# JUMP_PI.net
KiCad netlist of a schematic drawn in Altium Designer
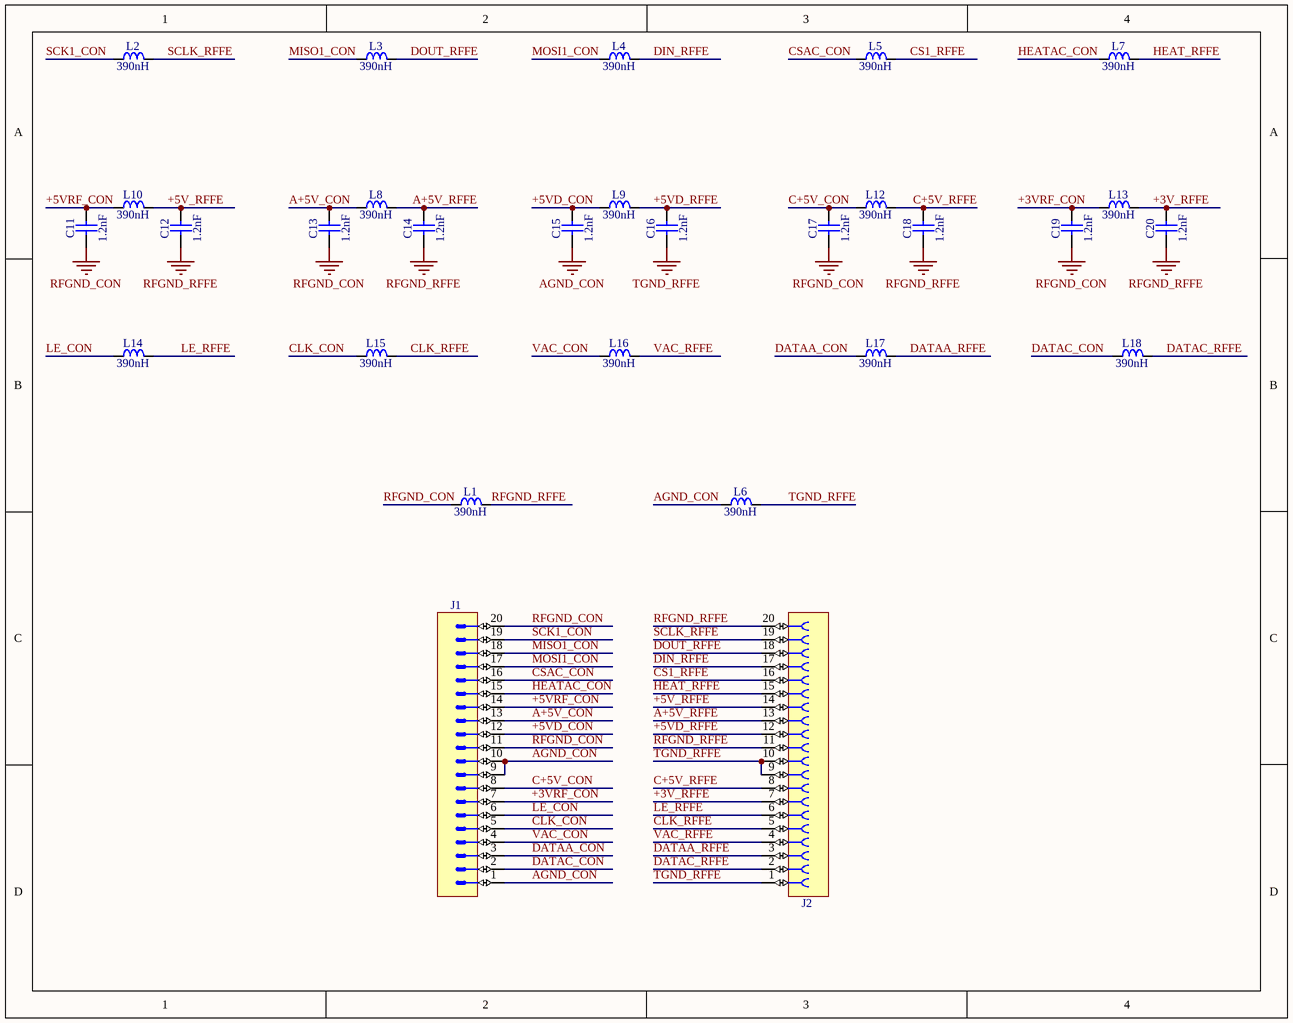
[diagram p0: JUMP_PI.schdoc]

(export (version "E")
  (design (tool "Eeschema 10.0.6"))
  (components
    (comp (ref "C11")
      (value "1.2nF")
      (footprint "CAPC2012X135N")
      (description "Non-polarised capacitor")
      (fields
        (field (name "PART NUMBER") "CC0805_1.2NF_50V_10%_X7R")
        (field (name "VOLTAGE") "50V")
        (field (name "AUTHOR") "CERN DEM JLC")
      )
      (libsource (lib "Capacitors") (part "Capacitor - non polarized"))
    )
    (comp (ref "C12")
      (value "1.2nF")
      (footprint "CAPC2012X135N")
      (description "Non-polarised capacitor")
      (fields
        (field (name "PART NUMBER") "CC0805_1.2NF_50V_10%_X7R")
        (field (name "VOLTAGE") "50V")
        (field (name "AUTHOR") "CERN DEM JLC")
      )
      (libsource (lib "Capacitors") (part "Capacitor - non polarized"))
    )
    (comp (ref "C13")
      (value "1.2nF")
      (footprint "CAPC2012X135N")
      (description "Non-polarised capacitor")
      (fields
        (field (name "PART NUMBER") "CC0805_1.2NF_50V_10%_X7R")
        (field (name "VOLTAGE") "50V")
        (field (name "AUTHOR") "CERN DEM JLC")
      )
      (libsource (lib "Capacitors") (part "Capacitor - non polarized"))
    )
    (comp (ref "C14")
      (value "1.2nF")
      (footprint "CAPC2012X135N")
      (description "Non-polarised capacitor")
      (fields
        (field (name "PART NUMBER") "CC0805_1.2NF_50V_10%_X7R")
        (field (name "VOLTAGE") "50V")
        (field (name "AUTHOR") "CERN DEM JLC")
      )
      (libsource (lib "Capacitors") (part "Capacitor - non polarized"))
    )
    (comp (ref "C15")
      (value "1.2nF")
      (footprint "CAPC2012X135N")
      (description "Non-polarised capacitor")
      (fields
        (field (name "PART NUMBER") "CC0805_1.2NF_50V_10%_X7R")
        (field (name "VOLTAGE") "50V")
        (field (name "AUTHOR") "CERN DEM JLC")
      )
      (libsource (lib "Capacitors") (part "Capacitor - non polarized"))
    )
    (comp (ref "C16")
      (value "1.2nF")
      (footprint "CAPC2012X135N")
      (description "Non-polarised capacitor")
      (fields
        (field (name "PART NUMBER") "CC0805_1.2NF_50V_10%_X7R")
        (field (name "VOLTAGE") "50V")
        (field (name "AUTHOR") "CERN DEM JLC")
      )
      (libsource (lib "Capacitors") (part "Capacitor - non polarized"))
    )
    (comp (ref "C17")
      (value "1.2nF")
      (footprint "CAPC2012X135N")
      (description "Non-polarised capacitor")
      (fields
        (field (name "PART NUMBER") "CC0805_1.2NF_50V_10%_X7R")
        (field (name "VOLTAGE") "50V")
        (field (name "AUTHOR") "CERN DEM JLC")
      )
      (libsource (lib "Capacitors") (part "Capacitor - non polarized"))
    )
    (comp (ref "C18")
      (value "1.2nF")
      (footprint "CAPC2012X135N")
      (description "Non-polarised capacitor")
      (fields
        (field (name "PART NUMBER") "CC0805_1.2NF_50V_10%_X7R")
        (field (name "VOLTAGE") "50V")
        (field (name "AUTHOR") "CERN DEM JLC")
      )
      (libsource (lib "Capacitors") (part "Capacitor - non polarized"))
    )
    (comp (ref "C19")
      (value "1.2nF")
      (footprint "CAPC2012X135N")
      (description "Non-polarised capacitor")
      (fields
        (field (name "PART NUMBER") "CC0805_1.2NF_50V_10%_X7R")
        (field (name "VOLTAGE") "50V")
        (field (name "AUTHOR") "CERN DEM JLC")
      )
      (libsource (lib "Capacitors") (part "Capacitor - non polarized"))
    )
    (comp (ref "C20")
      (value "1.2nF")
      (footprint "CAPC2012X135N")
      (description "Non-polarised capacitor")
      (fields
        (field (name "PART NUMBER") "CC0805_1.2NF_50V_10%_X7R")
        (field (name "VOLTAGE") "50V")
        (field (name "AUTHOR") "CERN DEM JLC")
      )
      (libsource (lib "Capacitors") (part "Capacitor - non polarized"))
    )
    (comp (ref "J1")
      (value "Header 20")
      (footprint "SAMTEC_TFM-120-01-L-S-RA")
      (description "Connector 20 Male")
      (fields
        (field (name "MANUFACTURER") "SAMTEC")
        (field (name "MANUFACTURER PART NUMBER") "TFM-120-01-L-S-RA")
        (field (name "AUTHOR") "LNLS DIG FCS")
      )
      (libsource (lib "Connectors_LNLS") (part "Connector 20 Male"))
    )
    (comp (ref "J2")
      (value "Header 20")
      (footprint "SAMTEC_SFM-120-02-S-SH")
      (description "Connector 20 Female")
      (fields
        (field (name "PART NUMBER") "SAMTEC_SFM-120-02-S-SH")
        (field (name "MANUFACTURER") "SAMTEC")
        (field (name "AUTHOR") "LNLS DIG FCS")
      )
      (libsource (lib "Connectors_LNLS") (part "Connector 20 Female"))
    )
    (comp (ref "L1")
      (value "390nH")
      (footprint "IND_ABRACON_AISC-0603")
      (description "Inductor")
      (fields
        (field (name "PART NUMBER") "IND_390NH_5%_ABRACON_AISC-0603")
        (field (name "POWER") "120mA")
        (field (name "AUTHOR") "CERN DEM JLC")
      )
      (libsource (lib "Inductors & Transformers") (part "Inductor"))
    )
    (comp (ref "L2")
      (value "390nH")
      (footprint "IND_ABRACON_AISC-0603")
      (description "Inductor")
      (fields
        (field (name "PART NUMBER") "IND_390NH_5%_ABRACON_AISC-0603")
        (field (name "POWER") "120mA")
        (field (name "AUTHOR") "CERN DEM JLC")
      )
      (libsource (lib "Inductors & Transformers") (part "Inductor"))
    )
    (comp (ref "L3")
      (value "390nH")
      (footprint "IND_ABRACON_AISC-0603")
      (description "Inductor")
      (fields
        (field (name "PART NUMBER") "IND_390NH_5%_ABRACON_AISC-0603")
        (field (name "POWER") "120mA")
        (field (name "AUTHOR") "CERN DEM JLC")
      )
      (libsource (lib "Inductors & Transformers") (part "Inductor"))
    )
    (comp (ref "L4")
      (value "390nH")
      (footprint "IND_ABRACON_AISC-0603")
      (description "Inductor")
      (fields
        (field (name "PART NUMBER") "IND_390NH_5%_ABRACON_AISC-0603")
        (field (name "POWER") "120mA")
        (field (name "AUTHOR") "CERN DEM JLC")
      )
      (libsource (lib "Inductors & Transformers") (part "Inductor"))
    )
    (comp (ref "L5")
      (value "390nH")
      (footprint "IND_ABRACON_AISC-0603")
      (description "Inductor")
      (fields
        (field (name "PART NUMBER") "IND_390NH_5%_ABRACON_AISC-0603")
        (field (name "POWER") "120mA")
        (field (name "AUTHOR") "CERN DEM JLC")
      )
      (libsource (lib "Inductors & Transformers") (part "Inductor"))
    )
    (comp (ref "L6")
      (value "390nH")
      (footprint "IND_ABRACON_AISC-0603")
      (description "Inductor")
      (fields
        (field (name "PART NUMBER") "IND_390NH_5%_ABRACON_AISC-0603")
        (field (name "POWER") "120mA")
        (field (name "AUTHOR") "CERN DEM JLC")
      )
      (libsource (lib "Inductors & Transformers") (part "Inductor"))
    )
    (comp (ref "L7")
      (value "390nH")
      (footprint "IND_ABRACON_AISC-0603")
      (description "Inductor")
      (fields
        (field (name "PART NUMBER") "IND_390NH_5%_ABRACON_AISC-0603")
        (field (name "POWER") "120mA")
        (field (name "AUTHOR") "CERN DEM JLC")
      )
      (libsource (lib "Inductors & Transformers") (part "Inductor"))
    )
    (comp (ref "L8")
      (value "390nH")
      (footprint "IND_ABRACON_AISC-0603")
      (description "Inductor")
      (fields
        (field (name "PART NUMBER") "IND_390NH_5%_ABRACON_AISC-0603")
        (field (name "POWER") "120mA")
        (field (name "AUTHOR") "CERN DEM JLC")
      )
      (libsource (lib "Inductors & Transformers") (part "Inductor"))
    )
    (comp (ref "L9")
      (value "390nH")
      (footprint "IND_ABRACON_AISC-0603")
      (description "Inductor")
      (fields
        (field (name "PART NUMBER") "IND_390NH_5%_ABRACON_AISC-0603")
        (field (name "POWER") "120mA")
        (field (name "AUTHOR") "CERN DEM JLC")
      )
      (libsource (lib "Inductors & Transformers") (part "Inductor"))
    )
    (comp (ref "L10")
      (value "390nH")
      (footprint "IND_ABRACON_AISC-0603")
      (description "Inductor")
      (fields
        (field (name "PART NUMBER") "IND_390NH_5%_ABRACON_AISC-0603")
        (field (name "POWER") "120mA")
        (field (name "AUTHOR") "CERN DEM JLC")
      )
      (libsource (lib "Inductors & Transformers") (part "Inductor"))
    )
    (comp (ref "L12")
      (value "390nH")
      (footprint "IND_ABRACON_AISC-0603")
      (description "Inductor")
      (fields
        (field (name "PART NUMBER") "IND_390NH_5%_ABRACON_AISC-0603")
        (field (name "POWER") "120mA")
        (field (name "AUTHOR") "CERN DEM JLC")
      )
      (libsource (lib "Inductors & Transformers") (part "Inductor"))
    )
    (comp (ref "L13")
      (value "390nH")
      (footprint "IND_ABRACON_AISC-0603")
      (description "Inductor")
      (fields
        (field (name "PART NUMBER") "IND_390NH_5%_ABRACON_AISC-0603")
        (field (name "POWER") "120mA")
        (field (name "AUTHOR") "CERN DEM JLC")
      )
      (libsource (lib "Inductors & Transformers") (part "Inductor"))
    )
    (comp (ref "L14")
      (value "390nH")
      (footprint "IND_ABRACON_AISC-0603")
      (description "Inductor")
      (fields
        (field (name "PART NUMBER") "IND_390NH_5%_ABRACON_AISC-0603")
        (field (name "POWER") "120mA")
        (field (name "AUTHOR") "CERN DEM JLC")
      )
      (libsource (lib "Inductors & Transformers") (part "Inductor"))
    )
    (comp (ref "L15")
      (value "390nH")
      (footprint "IND_ABRACON_AISC-0603")
      (description "Inductor")
      (fields
        (field (name "PART NUMBER") "IND_390NH_5%_ABRACON_AISC-0603")
        (field (name "POWER") "120mA")
        (field (name "AUTHOR") "CERN DEM JLC")
      )
      (libsource (lib "Inductors & Transformers") (part "Inductor"))
    )
    (comp (ref "L16")
      (value "390nH")
      (footprint "IND_ABRACON_AISC-0603")
      (description "Inductor")
      (fields
        (field (name "PART NUMBER") "IND_390NH_5%_ABRACON_AISC-0603")
        (field (name "POWER") "120mA")
        (field (name "AUTHOR") "CERN DEM JLC")
      )
      (libsource (lib "Inductors & Transformers") (part "Inductor"))
    )
    (comp (ref "L17")
      (value "390nH")
      (footprint "IND_ABRACON_AISC-0603")
      (description "Inductor")
      (fields
        (field (name "PART NUMBER") "IND_390NH_5%_ABRACON_AISC-0603")
        (field (name "POWER") "120mA")
        (field (name "AUTHOR") "CERN DEM JLC")
      )
      (libsource (lib "Inductors & Transformers") (part "Inductor"))
    )
    (comp (ref "L18")
      (value "390nH")
      (footprint "IND_ABRACON_AISC-0603")
      (description "Inductor")
      (fields
        (field (name "PART NUMBER") "IND_390NH_5%_ABRACON_AISC-0603")
        (field (name "POWER") "120mA")
        (field (name "AUTHOR") "CERN DEM JLC")
      )
      (libsource (lib "Inductors & Transformers") (part "Inductor"))
    )
  )
  (nets
    (net (code "1") (name "/+3VRF_CON") (class "Default")
      (node (ref "C19") (pin "2") (pinfunction "2_2") (pintype "passive"))
      (node (ref "J1") (pin "7") (pinfunction "7_7") (pintype "bidirectional"))
      (node (ref "L13") (pin "1") (pinfunction "1_1") (pintype "passive"))
    )
    (net (code "2") (name "/+3V_RFFE") (class "Default")
      (node (ref "C20") (pin "2") (pinfunction "2_2") (pintype "passive"))
      (node (ref "J2") (pin "7") (pinfunction "7_7") (pintype "bidirectional"))
      (node (ref "L13") (pin "2") (pinfunction "2_2") (pintype "passive"))
    )
    (net (code "3") (name "/+5VD_CON") (class "Default")
      (node (ref "C15") (pin "2") (pinfunction "2_2") (pintype "passive"))
      (node (ref "J1") (pin "12") (pinfunction "12_12") (pintype "bidirectional"))
      (node (ref "L9") (pin "1") (pinfunction "1_1") (pintype "passive"))
    )
    (net (code "4") (name "/+5VD_RFFE") (class "Default")
      (node (ref "C16") (pin "2") (pinfunction "2_2") (pintype "passive"))
      (node (ref "J2") (pin "12") (pinfunction "12_12") (pintype "bidirectional"))
      (node (ref "L9") (pin "2") (pinfunction "2_2") (pintype "passive"))
    )
    (net (code "5") (name "/+5VRF_CON") (class "Default")
      (node (ref "C11") (pin "2") (pinfunction "2_2") (pintype "passive"))
      (node (ref "J1") (pin "14") (pinfunction "14_14") (pintype "bidirectional"))
      (node (ref "L10") (pin "1") (pinfunction "1_1") (pintype "passive"))
    )
    (net (code "6") (name "/+5V_RFFE") (class "Default")
      (node (ref "C12") (pin "2") (pinfunction "2_2") (pintype "passive"))
      (node (ref "J2") (pin "14") (pinfunction "14_14") (pintype "bidirectional"))
      (node (ref "L10") (pin "2") (pinfunction "2_2") (pintype "passive"))
    )
    (net (code "7") (name "/A+5V_CON") (class "Default")
      (node (ref "C13") (pin "2") (pinfunction "2_2") (pintype "passive"))
      (node (ref "J1") (pin "13") (pinfunction "13_13") (pintype "bidirectional"))
      (node (ref "L8") (pin "1") (pinfunction "1_1") (pintype "passive"))
    )
    (net (code "8") (name "/A+5V_RFFE") (class "Default")
      (node (ref "C14") (pin "2") (pinfunction "2_2") (pintype "passive"))
      (node (ref "J2") (pin "13") (pinfunction "13_13") (pintype "bidirectional"))
      (node (ref "L8") (pin "2") (pinfunction "2_2") (pintype "passive"))
    )
    (net (code "9") (name "/C+5V_CON") (class "Default")
      (node (ref "C17") (pin "2") (pinfunction "2_2") (pintype "passive"))
      (node (ref "J1") (pin "8") (pinfunction "8_8") (pintype "bidirectional"))
      (node (ref "L12") (pin "1") (pinfunction "1_1") (pintype "passive"))
    )
    (net (code "10") (name "/C+5V_RFFE") (class "Default")
      (node (ref "C18") (pin "2") (pinfunction "2_2") (pintype "passive"))
      (node (ref "J2") (pin "8") (pinfunction "8_8") (pintype "bidirectional"))
      (node (ref "L12") (pin "2") (pinfunction "2_2") (pintype "passive"))
    )
    (net (code "11") (name "/CLK_CON") (class "Default")
      (node (ref "J1") (pin "5") (pinfunction "5_5") (pintype "bidirectional"))
      (node (ref "L15") (pin "1") (pinfunction "1_1") (pintype "passive"))
    )
    (net (code "12") (name "/CLK_RFFE") (class "Default")
      (node (ref "J2") (pin "5") (pinfunction "5_5") (pintype "bidirectional"))
      (node (ref "L15") (pin "2") (pinfunction "2_2") (pintype "passive"))
    )
    (net (code "13") (name "/CS1_RFFE") (class "Default")
      (node (ref "J2") (pin "16") (pinfunction "16_16") (pintype "bidirectional"))
      (node (ref "L5") (pin "2") (pinfunction "2_2") (pintype "passive"))
    )
    (net (code "14") (name "/CSAC_CON") (class "Default")
      (node (ref "J1") (pin "16") (pinfunction "16_16") (pintype "bidirectional"))
      (node (ref "L5") (pin "1") (pinfunction "1_1") (pintype "passive"))
    )
    (net (code "15") (name "/DATAA_CON") (class "Default")
      (node (ref "J1") (pin "3") (pinfunction "3_3") (pintype "bidirectional"))
      (node (ref "L17") (pin "1") (pinfunction "1_1") (pintype "passive"))
    )
    (net (code "16") (name "/DATAA_RFFE") (class "Default")
      (node (ref "J2") (pin "3") (pinfunction "3_3") (pintype "bidirectional"))
      (node (ref "L17") (pin "2") (pinfunction "2_2") (pintype "passive"))
    )
    (net (code "17") (name "/DATAC_CON") (class "Default")
      (node (ref "J1") (pin "2") (pinfunction "2_2") (pintype "bidirectional"))
      (node (ref "L18") (pin "1") (pinfunction "1_1") (pintype "passive"))
    )
    (net (code "18") (name "/DATAC_RFFE") (class "Default")
      (node (ref "J2") (pin "2") (pinfunction "2_2") (pintype "bidirectional"))
      (node (ref "L18") (pin "2") (pinfunction "2_2") (pintype "passive"))
    )
    (net (code "19") (name "/DIN_RFFE") (class "Default")
      (node (ref "J2") (pin "17") (pinfunction "17_17") (pintype "bidirectional"))
      (node (ref "L4") (pin "2") (pinfunction "2_2") (pintype "passive"))
    )
    (net (code "20") (name "/DOUT_RFFE") (class "Default")
      (node (ref "J2") (pin "18") (pinfunction "18_18") (pintype "bidirectional"))
      (node (ref "L3") (pin "2") (pinfunction "2_2") (pintype "passive"))
    )
    (net (code "21") (name "/HEATAC_CON") (class "Default")
      (node (ref "J1") (pin "15") (pinfunction "15_15") (pintype "bidirectional"))
      (node (ref "L7") (pin "1") (pinfunction "1_1") (pintype "passive"))
    )
    (net (code "22") (name "/HEAT_RFFE") (class "Default")
      (node (ref "J2") (pin "15") (pinfunction "15_15") (pintype "bidirectional"))
      (node (ref "L7") (pin "2") (pinfunction "2_2") (pintype "passive"))
    )
    (net (code "23") (name "/LE_CON") (class "Default")
      (node (ref "J1") (pin "6") (pinfunction "6_6") (pintype "bidirectional"))
      (node (ref "L14") (pin "1") (pinfunction "1_1") (pintype "passive"))
    )
    (net (code "24") (name "/LE_RFFE") (class "Default")
      (node (ref "J2") (pin "6") (pinfunction "6_6") (pintype "bidirectional"))
      (node (ref "L14") (pin "2") (pinfunction "2_2") (pintype "passive"))
    )
    (net (code "25") (name "/MISO1_CON") (class "Default")
      (node (ref "J1") (pin "18") (pinfunction "18_18") (pintype "bidirectional"))
      (node (ref "L3") (pin "1") (pinfunction "1_1") (pintype "passive"))
    )
    (net (code "26") (name "/MOSI1_CON") (class "Default")
      (node (ref "J1") (pin "17") (pinfunction "17_17") (pintype "bidirectional"))
      (node (ref "L4") (pin "1") (pinfunction "1_1") (pintype "passive"))
    )
    (net (code "27") (name "/SCK1_CON") (class "Default")
      (node (ref "J1") (pin "19") (pinfunction "19_19") (pintype "bidirectional"))
      (node (ref "L2") (pin "1") (pinfunction "1_1") (pintype "passive"))
    )
    (net (code "28") (name "/SCLK_RFFE") (class "Default")
      (node (ref "J2") (pin "19") (pinfunction "19_19") (pintype "bidirectional"))
      (node (ref "L2") (pin "2") (pinfunction "2_2") (pintype "passive"))
    )
    (net (code "29") (name "/VAC_CON") (class "Default")
      (node (ref "J1") (pin "4") (pinfunction "4_4") (pintype "bidirectional"))
      (node (ref "L16") (pin "1") (pinfunction "1_1") (pintype "passive"))
    )
    (net (code "30") (name "/VAC_RFFE") (class "Default")
      (node (ref "J2") (pin "4") (pinfunction "4_4") (pintype "bidirectional"))
      (node (ref "L16") (pin "2") (pinfunction "2_2") (pintype "passive"))
    )
    (net (code "31") (name "AGND_CON") (class "Default")
      (node (ref "C15") (pin "1") (pinfunction "1_1") (pintype "passive"))
      (node (ref "J1") (pin "1") (pinfunction "1_1") (pintype "bidirectional"))
      (node (ref "J1") (pin "10") (pinfunction "10_10") (pintype "bidirectional"))
      (node (ref "J1") (pin "9") (pinfunction "9_9") (pintype "bidirectional"))
      (node (ref "L6") (pin "1") (pinfunction "1_1") (pintype "passive"))
    )
    (net (code "32") (name "RFGND_CON") (class "Default")
      (node (ref "C11") (pin "1") (pinfunction "1_1") (pintype "passive"))
      (node (ref "C13") (pin "1") (pinfunction "1_1") (pintype "passive"))
      (node (ref "C17") (pin "1") (pinfunction "1_1") (pintype "passive"))
      (node (ref "C19") (pin "1") (pinfunction "1_1") (pintype "passive"))
      (node (ref "J1") (pin "11") (pinfunction "11_11") (pintype "bidirectional"))
      (node (ref "J1") (pin "20") (pinfunction "20_20") (pintype "bidirectional"))
      (node (ref "L1") (pin "1") (pinfunction "1_1") (pintype "passive"))
    )
    (net (code "33") (name "RFGND_RFFE") (class "Default")
      (node (ref "C12") (pin "1") (pinfunction "1_1") (pintype "passive"))
      (node (ref "C14") (pin "1") (pinfunction "1_1") (pintype "passive"))
      (node (ref "C18") (pin "1") (pinfunction "1_1") (pintype "passive"))
      (node (ref "C20") (pin "1") (pinfunction "1_1") (pintype "passive"))
      (node (ref "J2") (pin "11") (pinfunction "11_11") (pintype "bidirectional"))
      (node (ref "J2") (pin "20") (pinfunction "20_20") (pintype "bidirectional"))
      (node (ref "L1") (pin "2") (pinfunction "2_2") (pintype "passive"))
    )
    (net (code "34") (name "TGND_RFFE") (class "Default")
      (node (ref "C16") (pin "1") (pinfunction "1_1") (pintype "passive"))
      (node (ref "J2") (pin "1") (pinfunction "1_1") (pintype "bidirectional"))
      (node (ref "J2") (pin "10") (pinfunction "10_10") (pintype "bidirectional"))
      (node (ref "J2") (pin "9") (pinfunction "9_9") (pintype "bidirectional"))
      (node (ref "L6") (pin "2") (pinfunction "2_2") (pintype "passive"))
    )
  )
)
